# AlmosFinalMC.net
KiCad netlist of a schematic drawn in EAGLE
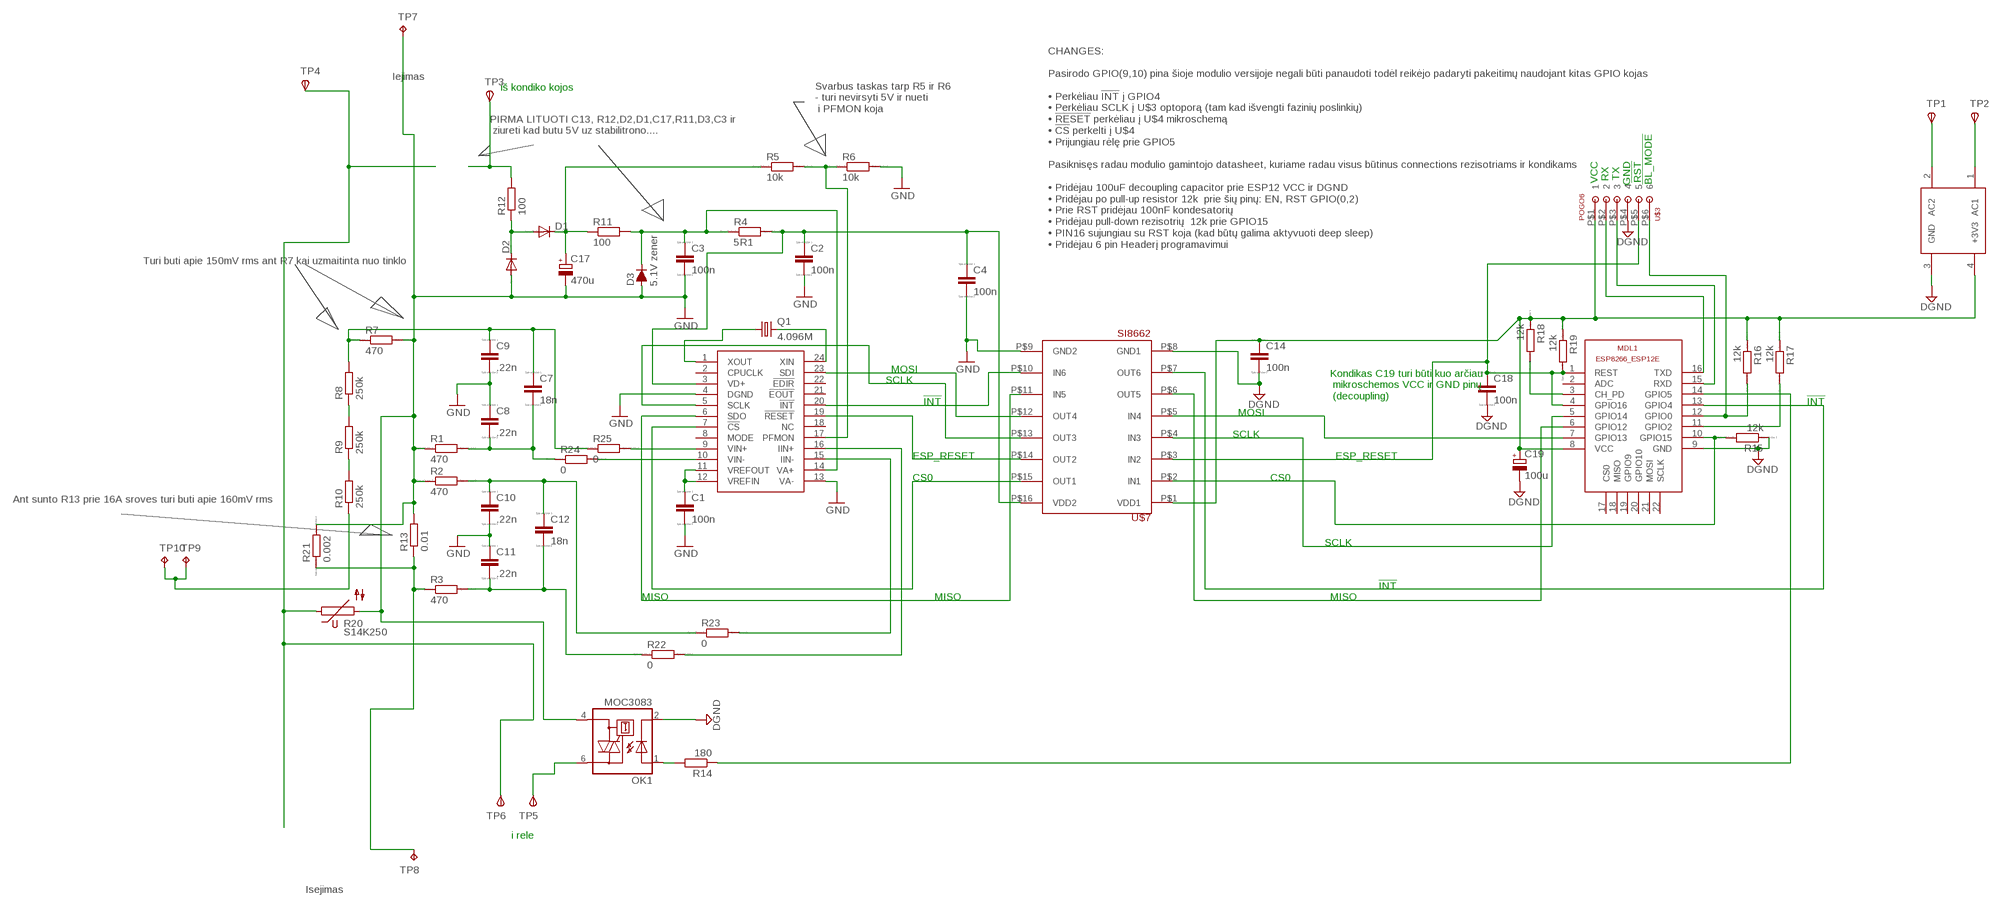
[diagram p0: schematic, sheet 1]

(export (version "E")
  (design (tool "Eeschema 10.0.6"))
  (components
    (comp (ref "C1")
      (value "100n")
      (footprint "eagle-import:C0603")
      (libsource (lib "eagle-import") (part "CC0603"))
    )
    (comp (ref "C2")
      (value "100n")
      (footprint "eagle-import:C0603")
      (libsource (lib "eagle-import") (part "CC0603"))
    )
    (comp (ref "C3")
      (value "100n")
      (footprint "eagle-import:C0603")
      (libsource (lib "eagle-import") (part "CC0603"))
    )
    (comp (ref "C4")
      (value "100n")
      (footprint "eagle-import:C0603")
      (libsource (lib "eagle-import") (part "CC0603"))
    )
    (comp (ref "C7")
      (value "18n")
      (footprint "eagle-import:C0603")
      (libsource (lib "eagle-import") (part "CC0603"))
    )
    (comp (ref "C8")
      (value ".22n")
      (footprint "eagle-import:C0603")
      (libsource (lib "eagle-import") (part "CC0603"))
    )
    (comp (ref "C9")
      (value ".22n")
      (footprint "eagle-import:C0603")
      (libsource (lib "eagle-import") (part "CC0603"))
    )
    (comp (ref "C10")
      (value ".22n")
      (footprint "eagle-import:C0603")
      (libsource (lib "eagle-import") (part "CC0603"))
    )
    (comp (ref "C11")
      (value ".22n")
      (footprint "eagle-import:C0603")
      (libsource (lib "eagle-import") (part "CC0603"))
    )
    (comp (ref "C12")
      (value "18n")
      (footprint "eagle-import:C0603")
      (libsource (lib "eagle-import") (part "CC0603"))
    )
    (comp (ref "C14")
      (value "100n")
      (footprint "eagle-import:C0603")
      (libsource (lib "eagle-import") (part "CC0603"))
    )
    (comp (ref "C17")
      (value "470u")
      (footprint "eagle-import:PANASONIC_G")
      (libsource (lib "eagle-import") (part "CPOL-EUG"))
    )
    (comp (ref "C18")
      (value "100n")
      (footprint "eagle-import:C0603")
      (libsource (lib "eagle-import") (part "CC0603"))
    )
    (comp (ref "C19")
      (value "100u")
      (footprint "eagle-import:UD-4X5,8_NICHICON")
      (libsource (lib "eagle-import") (part "CPOL-EUUD-4X5,8"))
    )
    (comp (ref "D1")
      (value "DIODE-DO-214AC")
      (footprint "eagle-import:DO-214AC")
      (libsource (lib "eagle-import") (part "DIODE-DO-214AC"))
    )
    (comp (ref "D2")
      (value "DIODE-DO-214AC")
      (footprint "eagle-import:DO-214AC")
      (libsource (lib "eagle-import") (part "DIODE-DO-214AC"))
    )
    (comp (ref "D3")
      (value "5.1V zener")
      (footprint "eagle-import:SOD123")
      (libsource (lib "eagle-import") (part "D-FILL-SOD123"))
    )
    (comp (ref "MDL1")
      (value "ESP8266-12EESP8266-ESP12E")
      (footprint "eagle-import:ESP8266-ESP12E")
      (libsource (lib "eagle-import") (part "ESP8266-12EESP8266-ESP12E"))
    )
    (comp (ref "OK1")
      (value "MOC3083")
      (footprint "eagle-import:DIL06")
      (fields (field (name "MF") "VISHAY/TELEFUNKEN") (field (name "MPN") "IL410"))
      (libsource (lib "eagle-import") (part "IL410"))
    )
    (comp (ref "Q1")
      (value "4.096M")
      (footprint "eagle-import:HC49UP")
      (libsource (lib "eagle-import") (part "CRYSTALHC49UP"))
    )
    (comp (ref "R1")
      (value "470")
      (footprint "eagle-import:R0603")
      (libsource (lib "eagle-import") (part "RR0603"))
    )
    (comp (ref "R2")
      (value "470")
      (footprint "eagle-import:R0603")
      (libsource (lib "eagle-import") (part "RR0603"))
    )
    (comp (ref "R3")
      (value "470")
      (footprint "eagle-import:R0603")
      (libsource (lib "eagle-import") (part "RR0603"))
    )
    (comp (ref "R4")
      (value "5R1")
      (footprint "eagle-import:R0805")
      (libsource (lib "eagle-import") (part "R"))
    )
    (comp (ref "R5")
      (value "10k")
      (footprint "eagle-import:R0603")
      (libsource (lib "eagle-import") (part "RR0603"))
    )
    (comp (ref "R6")
      (value "10k")
      (footprint "eagle-import:R0603")
      (libsource (lib "eagle-import") (part "RR0603"))
    )
    (comp (ref "R7")
      (value "470")
      (footprint "eagle-import:R0805")
      (libsource (lib "eagle-import") (part "R"))
    )
    (comp (ref "R8")
      (value "250k")
      (footprint "eagle-import:0204_7")
      (libsource (lib "eagle-import") (part "R-EU_0204/7"))
    )
    (comp (ref "R9")
      (value "250k")
      (footprint "eagle-import:0204_7")
      (libsource (lib "eagle-import") (part "R-EU_0204/7"))
    )
    (comp (ref "R10")
      (value "250k")
      (footprint "eagle-import:0204_7")
      (libsource (lib "eagle-import") (part "R-EU_0204/7"))
    )
    (comp (ref "R11")
      (value "100")
      (footprint "eagle-import:0207_5V")
      (libsource (lib "eagle-import") (part "R-EU_0207/5V"))
    )
    (comp (ref "R12")
      (value "100")
      (footprint "eagle-import:0309_10")
      (libsource (lib "eagle-import") (part "R-EU_0309/10"))
    )
    (comp (ref "R13")
      (value "0.01")
      (footprint "eagle-import:V235_17")
      (libsource (lib "eagle-import") (part "R-EU_V235/17"))
    )
    (comp (ref "R14")
      (value "180")
      (footprint "eagle-import:R0603")
      (libsource (lib "eagle-import") (part "R-EU_R0603"))
    )
    (comp (ref "R15")
      (value "12k")
      (footprint "eagle-import:R0603")
      (libsource (lib "eagle-import") (part "RR0603"))
    )
    (comp (ref "R16")
      (value "12k")
      (footprint "eagle-import:R0603")
      (libsource (lib "eagle-import") (part "RR0603"))
    )
    (comp (ref "R17")
      (value "12k")
      (footprint "eagle-import:R0603")
      (libsource (lib "eagle-import") (part "RR0603"))
    )
    (comp (ref "R18")
      (value "12k")
      (footprint "eagle-import:R0603")
      (libsource (lib "eagle-import") (part "RR0603"))
    )
    (comp (ref "R19")
      (value "12k")
      (footprint "eagle-import:R0603")
      (libsource (lib "eagle-import") (part "RR0603"))
    )
    (comp (ref "R20")
      (value "S14K250")
      (footprint "eagle-import:S14K250")
      (libsource (lib "eagle-import") (part "S14K250"))
    )
    (comp (ref "R21")
      (value "0.002")
      (footprint "eagle-import:R2512")
      (libsource (lib "eagle-import") (part "RR2512"))
    )
    (comp (ref "R22")
      (value "0")
      (footprint "eagle-import:R0603")
      (libsource (lib "eagle-import") (part "RR0603"))
    )
    (comp (ref "R23")
      (value "0")
      (footprint "eagle-import:R0603")
      (libsource (lib "eagle-import") (part "RR0603"))
    )
    (comp (ref "R24")
      (value "0")
      (footprint "eagle-import:R0603")
      (libsource (lib "eagle-import") (part "RR0603"))
    )
    (comp (ref "R25")
      (value "0")
      (footprint "eagle-import:R0603")
      (libsource (lib "eagle-import") (part "RR0603"))
    )
    (comp (ref "TP1")
      (value "TPSPAD1-13Y")
      (footprint "eagle-import:P1-13Y")
      (libsource (lib "eagle-import") (part "TPSPAD1-13Y"))
    )
    (comp (ref "TP2")
      (value "TPSPAD1-13Y")
      (footprint "eagle-import:P1-13Y")
      (libsource (lib "eagle-import") (part "TPSPAD1-13Y"))
    )
    (comp (ref "TP3")
      (value "TPSPAD1-13Y")
      (footprint "eagle-import:P1-13Y")
      (libsource (lib "eagle-import") (part "TPSPAD1-13Y"))
    )
    (comp (ref "TP4")
      (value "TPSPAD1-13Y")
      (footprint "eagle-import:P1-13Y")
      (libsource (lib "eagle-import") (part "TPSPAD1-13Y"))
    )
    (comp (ref "TP5")
      (value "TPSPAD1-13Y")
      (footprint "eagle-import:P1-13Y")
      (libsource (lib "eagle-import") (part "TPSPAD1-13Y"))
    )
    (comp (ref "TP6")
      (value "TPSPAD1-13Y")
      (footprint "eagle-import:P1-13Y")
      (libsource (lib "eagle-import") (part "TPSPAD1-13Y"))
    )
    (comp (ref "TP7")
      (value "TPPAD1-20")
      (footprint "eagle-import:P1-20")
      (libsource (lib "eagle-import") (part "TPPAD1-20"))
    )
    (comp (ref "TP8")
      (value "TPPAD1-20")
      (footprint "eagle-import:P1-20")
      (libsource (lib "eagle-import") (part "TPPAD1-20"))
    )
    (comp (ref "TP9")
      (value "TPPAD1-13")
      (footprint "eagle-import:P1-13")
      (libsource (lib "eagle-import") (part "TPPAD1-13"))
    )
    (comp (ref "TP10")
      (value "TPPAD1-13")
      (footprint "eagle-import:P1-13")
      (libsource (lib "eagle-import") (part "TPPAD1-13"))
    )
    (comp (ref "U$1")
      (value "CS5460A")
      (footprint "eagle-import:SSOP24")
      (libsource (lib "eagle-import") (part "CS5460A"))
    )
    (comp (ref "U$3")
      (value "POGO6")
      (footprint "eagle-import:POGO6")
      (libsource (lib "eagle-import") (part "POGO6"))
    )
    (comp (ref "U$5")
      (value "RAC02")
      (footprint "eagle-import:RAC02")
      (libsource (lib "eagle-import") (part "RAC02"))
    )
    (comp (ref "U$7")
      (value "SI8662")
      (footprint "eagle-import:SOIC8")
      (libsource (lib "eagle-import") (part "SI8662"))
    )
  )
  (nets
    (net (code "1") (name "DGND") (class "Default")
      (node (ref "C14") (pin "2") (pinfunction "2_2") (pintype "passive"))
      (node (ref "C18") (pin "2") (pinfunction "2_2") (pintype "passive"))
      (node (ref "C19") (pin "-") (pinfunction "-_-") (pintype "passive"))
      (node (ref "MDL1") (pin "9") (pinfunction "GND_9") (pintype "bidirectional"))
      (node (ref "OK1") (pin "2") (pinfunction "C_2") (pintype "passive"))
      (node (ref "R15") (pin "1") (pinfunction "1_1") (pintype "passive"))
      (node (ref "U$3") (pin "P$4") (pinfunction "4_P$4") (pintype "bidirectional"))
      (node (ref "U$5") (pin "3") (pinfunction "GND_3") (pintype "bidirectional"))
      (node (ref "U$7") (pin "P$8") (pinfunction "GND1_P$8") (pintype "bidirectional"))
    )
    (net (code "2") (name "GND") (class "Default")
      (node (ref "C1") (pin "2") (pinfunction "2_2") (pintype "passive"))
      (node (ref "C10") (pin "2") (pinfunction "2_2") (pintype "passive"))
      (node (ref "C11") (pin "1") (pinfunction "1_1") (pintype "passive"))
      (node (ref "C17") (pin "-") (pinfunction "-_-") (pintype "passive"))
      (node (ref "C2") (pin "2") (pinfunction "2_2") (pintype "passive"))
      (node (ref "C3") (pin "2") (pinfunction "2_2") (pintype "passive"))
      (node (ref "C4") (pin "2") (pinfunction "2_2") (pintype "passive"))
      (node (ref "C8") (pin "1") (pinfunction "1_1") (pintype "passive"))
      (node (ref "C9") (pin "2") (pinfunction "2_2") (pintype "passive"))
      (node (ref "D2") (pin "A") (pinfunction "A_A") (pintype "passive"))
      (node (ref "D3") (pin "2") (pinfunction "A_2") (pintype "passive"))
      (node (ref "OK1") (pin "4") (pinfunction "A1_4") (pintype "passive"))
      (node (ref "R1") (pin "1") (pinfunction "1_1") (pintype "passive"))
      (node (ref "R13") (pin "2") (pinfunction "2_2") (pintype "passive"))
      (node (ref "R2") (pin "1") (pinfunction "1_1") (pintype "passive"))
      (node (ref "R20") (pin "2") (pinfunction "2_2") (pintype "passive"))
      (node (ref "R21") (pin "2") (pinfunction "2_2") (pintype "passive"))
      (node (ref "R6") (pin "2") (pinfunction "2_2") (pintype "passive"))
      (node (ref "R7") (pin "2") (pinfunction "2_2") (pintype "passive"))
      (node (ref "TP7") (pin "TP") (pinfunction "TP_TP") (pintype "input"))
      (node (ref "U$1") (pin "13") (pinfunction "VA-_13") (pintype "bidirectional"))
      (node (ref "U$1") (pin "4") (pinfunction "DGND_4") (pintype "bidirectional"))
      (node (ref "U$7") (pin "P$9") (pinfunction "GND2_P$9") (pintype "bidirectional"))
    )
    (net (code "3") (name "Net-(C7-Pad1)") (class "Default")
      (node (ref "C7") (pin "1") (pinfunction "1_1") (pintype "passive"))
      (node (ref "C9") (pin "1") (pinfunction "1_1") (pintype "passive"))
      (node (ref "R25") (pin "1") (pinfunction "1_1") (pintype "passive"))
      (node (ref "R7") (pin "1") (pinfunction "1_1") (pintype "passive"))
      (node (ref "R8") (pin "2") (pinfunction "2_2") (pintype "passive"))
    )
    (net (code "4") (name "Net-(C7-Pad2)") (class "Default")
      (node (ref "C7") (pin "2") (pinfunction "2_2") (pintype "passive"))
      (node (ref "C8") (pin "2") (pinfunction "2_2") (pintype "passive"))
      (node (ref "R1") (pin "2") (pinfunction "2_2") (pintype "passive"))
      (node (ref "R24") (pin "1") (pinfunction "1_1") (pintype "passive"))
    )
    (net (code "5") (name "Net-(C10-Pad1)") (class "Default")
      (node (ref "C10") (pin "1") (pinfunction "1_1") (pintype "passive"))
      (node (ref "C12") (pin "1") (pinfunction "1_1") (pintype "passive"))
      (node (ref "R2") (pin "2") (pinfunction "2_2") (pintype "passive"))
      (node (ref "R23") (pin "1") (pinfunction "1_1") (pintype "passive"))
    )
    (net (code "6") (name "Net-(C11-Pad2)") (class "Default")
      (node (ref "C11") (pin "2") (pinfunction "2_2") (pintype "passive"))
      (node (ref "C12") (pin "2") (pinfunction "2_2") (pintype "passive"))
      (node (ref "R22") (pin "1") (pinfunction "1_1") (pintype "passive"))
      (node (ref "R3") (pin "2") (pinfunction "2_2") (pintype "passive"))
    )
    (net (code "7") (name "Net-(C17-Pad+)") (class "Default")
      (node (ref "C17") (pin "+") (pinfunction "+_+") (pintype "passive"))
      (node (ref "D1") (pin "C") (pinfunction "C_C") (pintype "passive"))
      (node (ref "R11") (pin "1") (pinfunction "1_1") (pintype "passive"))
      (node (ref "R5") (pin "1") (pinfunction "1_1") (pintype "passive"))
    )
    (net (code "8") (name "Net-(D1-PadA)") (class "Default")
      (node (ref "D1") (pin "A") (pinfunction "A_A") (pintype "passive"))
      (node (ref "D2") (pin "C") (pinfunction "C_C") (pintype "passive"))
      (node (ref "R12") (pin "1") (pinfunction "1_1") (pintype "passive"))
    )
    (net (code "9") (name "Net-(D3-C)") (class "Default")
      (node (ref "C3") (pin "1") (pinfunction "1_1") (pintype "passive"))
      (node (ref "D3") (pin "1") (pinfunction "C_1") (pintype "passive"))
      (node (ref "R11") (pin "2") (pinfunction "2_2") (pintype "passive"))
      (node (ref "R4") (pin "1") (pinfunction "1_1") (pintype "passive"))
      (node (ref "U$1") (pin "14") (pinfunction "VA+_14") (pintype "bidirectional"))
    )
    (net (code "10") (name "Net-(MDL1-CH_PD)") (class "Default")
      (node (ref "MDL1") (pin "3") (pinfunction "CH_PD_3") (pintype "bidirectional"))
      (node (ref "R18") (pin "2") (pinfunction "2_2") (pintype "passive"))
    )
    (net (code "11") (name "Net-(MDL1-GPIO0)") (class "Default")
      (node (ref "MDL1") (pin "12") (pinfunction "GPIO0_12") (pintype "bidirectional"))
      (node (ref "R16") (pin "2") (pinfunction "2_2") (pintype "passive"))
      (node (ref "U$3") (pin "P$6") (pinfunction "6_P$6") (pintype "bidirectional"))
    )
    (net (code "12") (name "Net-(MDL1-GPIO2)") (class "Default")
      (node (ref "MDL1") (pin "11") (pinfunction "GPIO2_11") (pintype "bidirectional"))
      (node (ref "R17") (pin "2") (pinfunction "2_2") (pintype "passive"))
    )
    (net (code "13") (name "Net-(MDL1-GPIO4)") (class "Default")
      (node (ref "MDL1") (pin "13") (pinfunction "GPIO4_13") (pintype "bidirectional"))
      (node (ref "U$7") (pin "P$7") (pinfunction "OUT6_P$7") (pintype "bidirectional"))
    )
    (net (code "14") (name "Net-(MDL1-GPIO5)") (class "Default")
      (node (ref "MDL1") (pin "14") (pinfunction "GPIO5_14") (pintype "bidirectional"))
      (node (ref "R14") (pin "1") (pinfunction "1_1") (pintype "passive"))
    )
    (net (code "15") (name "Net-(MDL1-GPIO12)") (class "Default")
      (node (ref "MDL1") (pin "6") (pinfunction "GPIO12_6") (pintype "bidirectional"))
      (node (ref "U$7") (pin "P$6") (pinfunction "OUT5_P$6") (pintype "bidirectional"))
    )
    (net (code "16") (name "Net-(MDL1-GPIO13)") (class "Default")
      (node (ref "MDL1") (pin "7") (pinfunction "GPIO13_7") (pintype "bidirectional"))
      (node (ref "U$7") (pin "P$5") (pinfunction "IN4_P$5") (pintype "bidirectional"))
    )
    (net (code "17") (name "Net-(MDL1-GPIO14)") (class "Default")
      (node (ref "MDL1") (pin "5") (pinfunction "GPIO14_5") (pintype "bidirectional"))
      (node (ref "U$7") (pin "P$4") (pinfunction "IN3_P$4") (pintype "bidirectional"))
    )
    (net (code "18") (name "Net-(MDL1-GPIO15)") (class "Default")
      (node (ref "MDL1") (pin "10") (pinfunction "GPIO15_10") (pintype "bidirectional"))
      (node (ref "R15") (pin "2") (pinfunction "2_2") (pintype "passive"))
      (node (ref "U$7") (pin "P$2") (pinfunction "IN1_P$2") (pintype "bidirectional"))
    )
    (net (code "19") (name "Net-(MDL1-GPIO16)") (class "Default")
      (node (ref "C18") (pin "1") (pinfunction "1_1") (pintype "passive"))
      (node (ref "MDL1") (pin "1") (pinfunction "REST_1") (pintype "bidirectional"))
      (node (ref "MDL1") (pin "4") (pinfunction "GPIO16_4") (pintype "bidirectional"))
      (node (ref "R19") (pin "2") (pinfunction "2_2") (pintype "passive"))
      (node (ref "U$3") (pin "P$5") (pinfunction "5_P$5") (pintype "bidirectional"))
      (node (ref "U$7") (pin "P$3") (pinfunction "IN2_P$3") (pintype "bidirectional"))
    )
    (net (code "20") (name "Net-(MDL1-RXD)") (class "Default")
      (node (ref "MDL1") (pin "15") (pinfunction "RXD_15") (pintype "bidirectional"))
      (node (ref "U$3") (pin "P$3") (pinfunction "3_P$3") (pintype "bidirectional"))
    )
    (net (code "21") (name "Net-(MDL1-TXD)") (class "Default")
      (node (ref "MDL1") (pin "16") (pinfunction "TXD_16") (pintype "bidirectional"))
      (node (ref "U$3") (pin "P$2") (pinfunction "2_P$2") (pintype "bidirectional"))
    )
    (net (code "22") (name "Net-(MDL1-VCC)") (class "Default")
      (node (ref "C14") (pin "1") (pinfunction "1_1") (pintype "passive"))
      (node (ref "C19") (pin "+") (pinfunction "+_+") (pintype "passive"))
      (node (ref "MDL1") (pin "8") (pinfunction "VCC_8") (pintype "bidirectional"))
      (node (ref "R16") (pin "1") (pinfunction "1_1") (pintype "passive"))
      (node (ref "R17") (pin "1") (pinfunction "1_1") (pintype "passive"))
      (node (ref "R18") (pin "1") (pinfunction "1_1") (pintype "passive"))
      (node (ref "R19") (pin "1") (pinfunction "1_1") (pintype "passive"))
      (node (ref "U$3") (pin "P$1") (pinfunction "1_P$1") (pintype "bidirectional"))
      (node (ref "U$5") (pin "4") (pinfunction "+3V3_4") (pintype "bidirectional"))
      (node (ref "U$7") (pin "P$1") (pinfunction "VDD1_P$1") (pintype "bidirectional"))
    )
    (net (code "23") (name "Net-(OK1-A)") (class "Default")
      (node (ref "OK1") (pin "1") (pinfunction "A_1") (pintype "passive"))
      (node (ref "R14") (pin "2") (pinfunction "2_2") (pintype "passive"))
    )
    (net (code "24") (name "Net-(OK1-A2)") (class "Default")
      (node (ref "OK1") (pin "6") (pinfunction "A2_6") (pintype "passive"))
      (node (ref "TP5") (pin "TP") (pinfunction "PP_TP") (pintype "input"))
    )
    (net (code "25") (name "Net-(R8-Pad1)") (class "Default")
      (node (ref "R8") (pin "1") (pinfunction "1_1") (pintype "passive"))
      (node (ref "R9") (pin "2") (pinfunction "2_2") (pintype "passive"))
    )
    (net (code "26") (name "Net-(R10-Pad1)") (class "Default")
      (node (ref "R10") (pin "1") (pinfunction "1_1") (pintype "passive"))
      (node (ref "TP10") (pin "TP") (pinfunction "TP_TP") (pintype "input"))
      (node (ref "TP9") (pin "TP") (pinfunction "TP_TP") (pintype "input"))
    )
    (net (code "27") (name "Net-(R10-Pad2)") (class "Default")
      (node (ref "R10") (pin "2") (pinfunction "2_2") (pintype "passive"))
      (node (ref "R9") (pin "1") (pinfunction "1_1") (pintype "passive"))
    )
    (net (code "28") (name "Net-(R13-Pad1)") (class "Default")
      (node (ref "R13") (pin "1") (pinfunction "1_1") (pintype "passive"))
      (node (ref "R21") (pin "1") (pinfunction "1_1") (pintype "passive"))
      (node (ref "R3") (pin "1") (pinfunction "1_1") (pintype "passive"))
      (node (ref "TP8") (pin "TP") (pinfunction "TP_TP") (pintype "input"))
    )
    (net (code "29") (name "Net-(TP1-PP)") (class "Default")
      (node (ref "TP1") (pin "TP") (pinfunction "PP_TP") (pintype "input"))
      (node (ref "U$5") (pin "2") (pinfunction "AC2_2") (pintype "bidirectional"))
    )
    (net (code "30") (name "Net-(TP2-PP)") (class "Default")
      (node (ref "TP2") (pin "TP") (pinfunction "PP_TP") (pintype "input"))
      (node (ref "U$5") (pin "1") (pinfunction "AC1_1") (pintype "bidirectional"))
    )
    (net (code "31") (name "Net-(TP3-PP)") (class "Default")
      (node (ref "R12") (pin "2") (pinfunction "2_2") (pintype "passive"))
      (node (ref "TP3") (pin "TP") (pinfunction "PP_TP") (pintype "input"))
    )
    (net (code "32") (name "Net-(TP4-PP)") (class "Default")
      (node (ref "R20") (pin "1") (pinfunction "1_1") (pintype "passive"))
      (node (ref "TP4") (pin "TP") (pinfunction "PP_TP") (pintype "input"))
      (node (ref "TP6") (pin "TP") (pinfunction "PP_TP") (pintype "input"))
    )
    (net (code "33") (name "Net-(U$1-IIN+)") (class "Default")
      (node (ref "R22") (pin "2") (pinfunction "2_2") (pintype "passive"))
      (node (ref "U$1") (pin "16") (pinfunction "IIN+_16") (pintype "bidirectional"))
    )
    (net (code "34") (name "Net-(U$1-IIN-)") (class "Default")
      (node (ref "R23") (pin "2") (pinfunction "2_2") (pintype "passive"))
      (node (ref "U$1") (pin "15") (pinfunction "IIN-_15") (pintype "bidirectional"))
    )
    (net (code "35") (name "Net-(U$1-PFMON)") (class "Default")
      (node (ref "R5") (pin "2") (pinfunction "2_2") (pintype "passive"))
      (node (ref "R6") (pin "1") (pinfunction "1_1") (pintype "passive"))
      (node (ref "U$1") (pin "17") (pinfunction "PFMON_17") (pintype "bidirectional"))
    )
    (net (code "36") (name "Net-(U$1-SCLK)") (class "Default")
      (node (ref "U$1") (pin "5") (pinfunction "SCLK_5") (pintype "bidirectional"))
      (node (ref "U$7") (pin "P$13") (pinfunction "OUT3_P$13") (pintype "bidirectional"))
    )
    (net (code "37") (name "Net-(U$1-SDI)") (class "Default")
      (node (ref "U$1") (pin "23") (pinfunction "SDI_23") (pintype "bidirectional"))
      (node (ref "U$7") (pin "P$12") (pinfunction "OUT4_P$12") (pintype "bidirectional"))
    )
    (net (code "38") (name "Net-(U$1-SDO)") (class "Default")
      (node (ref "U$1") (pin "6") (pinfunction "SDO_6") (pintype "bidirectional"))
      (node (ref "U$7") (pin "P$11") (pinfunction "IN5_P$11") (pintype "bidirectional"))
    )
    (net (code "39") (name "Net-(U$1-VD+)") (class "Default")
      (node (ref "C2") (pin "1") (pinfunction "1_1") (pintype "passive"))
      (node (ref "C4") (pin "1") (pinfunction "1_1") (pintype "passive"))
      (node (ref "R4") (pin "2") (pinfunction "2_2") (pintype "passive"))
      (node (ref "U$1") (pin "3") (pinfunction "VD+_3") (pintype "bidirectional"))
      (node (ref "U$7") (pin "P$16") (pinfunction "VDD2_P$16") (pintype "bidirectional"))
    )
    (net (code "40") (name "Net-(U$1-VIN+)") (class "Default")
      (node (ref "R25") (pin "2") (pinfunction "2_2") (pintype "passive"))
      (node (ref "U$1") (pin "9") (pinfunction "VIN+_9") (pintype "bidirectional"))
    )
    (net (code "41") (name "Net-(U$1-VIN-)") (class "Default")
      (node (ref "R24") (pin "2") (pinfunction "2_2") (pintype "passive"))
      (node (ref "U$1") (pin "10") (pinfunction "VIN-_10") (pintype "bidirectional"))
    )
    (net (code "42") (name "Net-(U$1-VREFIN)") (class "Default")
      (node (ref "C1") (pin "1") (pinfunction "1_1") (pintype "passive"))
      (node (ref "U$1") (pin "11") (pinfunction "VREFOUT_11") (pintype "bidirectional"))
      (node (ref "U$1") (pin "12") (pinfunction "VREFIN_12") (pintype "bidirectional"))
    )
    (net (code "43") (name "Net-(U$1-XIN)") (class "Default")
      (node (ref "Q1") (pin "2") (pinfunction "2_2") (pintype "passive"))
      (node (ref "U$1") (pin "24") (pinfunction "XIN_24") (pintype "bidirectional"))
    )
    (net (code "44") (name "Net-(U$1-XOUT)") (class "Default")
      (node (ref "Q1") (pin "1") (pinfunction "1_1") (pintype "passive"))
      (node (ref "U$1") (pin "1") (pinfunction "XOUT_1") (pintype "bidirectional"))
    )
    (net (code "45") (name "Net-(U$1-~{CS})") (class "Default")
      (node (ref "U$1") (pin "7") (pinfunction "~{CS}_7") (pintype "bidirectional"))
      (node (ref "U$7") (pin "P$15") (pinfunction "OUT1_P$15") (pintype "bidirectional"))
    )
    (net (code "46") (name "Net-(U$1-~{INT})") (class "Default")
      (node (ref "U$1") (pin "20") (pinfunction "~{INT}_20") (pintype "bidirectional"))
      (node (ref "U$7") (pin "P$10") (pinfunction "IN6_P$10") (pintype "bidirectional"))
    )
    (net (code "47") (name "Net-(U$1-~{RESET})") (class "Default")
      (node (ref "U$1") (pin "19") (pinfunction "~{RESET}_19") (pintype "bidirectional"))
      (node (ref "U$7") (pin "P$14") (pinfunction "OUT2_P$14") (pintype "bidirectional"))
    )
    (net (code "48") (name "unconnected-(MDL1-ADC-Pad2)") (class "Default")
      (node (ref "MDL1") (pin "2") (pinfunction "ADC_2") (pintype "bidirectional"))
    )
    (net (code "49") (name "unconnected-(MDL1-CS0-Pad17)") (class "Default")
      (node (ref "MDL1") (pin "17") (pinfunction "CS0_17") (pintype "bidirectional"))
    )
    (net (code "50") (name "unconnected-(MDL1-GPIO9-Pad19)") (class "Default")
      (node (ref "MDL1") (pin "19") (pinfunction "GPIO9_19") (pintype "bidirectional"))
    )
    (net (code "51") (name "unconnected-(MDL1-GPIO10-Pad20)") (class "Default")
      (node (ref "MDL1") (pin "20") (pinfunction "GPIO10_20") (pintype "bidirectional"))
    )
    (net (code "52") (name "unconnected-(MDL1-MISO-Pad18)") (class "Default")
      (node (ref "MDL1") (pin "18") (pinfunction "MISO_18") (pintype "bidirectional"))
    )
    (net (code "53") (name "unconnected-(MDL1-MOSI-Pad21)") (class "Default")
      (node (ref "MDL1") (pin "21") (pinfunction "MOSI_21") (pintype "bidirectional"))
    )
    (net (code "54") (name "unconnected-(MDL1-SCLK-Pad22)") (class "Default")
      (node (ref "MDL1") (pin "22") (pinfunction "SCLK_22") (pintype "bidirectional"))
    )
    (net (code "55") (name "unconnected-(U$1-CPUCLK-Pad2)") (class "Default")
      (node (ref "U$1") (pin "2") (pinfunction "CPUCLK_2") (pintype "bidirectional"))
    )
    (net (code "56") (name "unconnected-(U$1-MODE-Pad8)") (class "Default")
      (node (ref "U$1") (pin "8") (pinfunction "MODE_8") (pintype "bidirectional"))
    )
    (net (code "57") (name "unconnected-(U$1-NC-Pad18)") (class "Default")
      (node (ref "U$1") (pin "18") (pinfunction "NC_18") (pintype "bidirectional"))
    )
    (net (code "58") (name "unconnected-(U$1-~{EDIR}-Pad22)") (class "Default")
      (node (ref "U$1") (pin "22") (pinfunction "~{EDIR}_22") (pintype "bidirectional"))
    )
    (net (code "59") (name "unconnected-(U$1-~{EOUT}-Pad21)") (class "Default")
      (node (ref "U$1") (pin "21") (pinfunction "~{EOUT}_21") (pintype "bidirectional"))
    )
  )
)
